# GSE_Controller_Schematic25_EasyEDA.net
KiCad netlist of a schematic drawn in EasyEDA
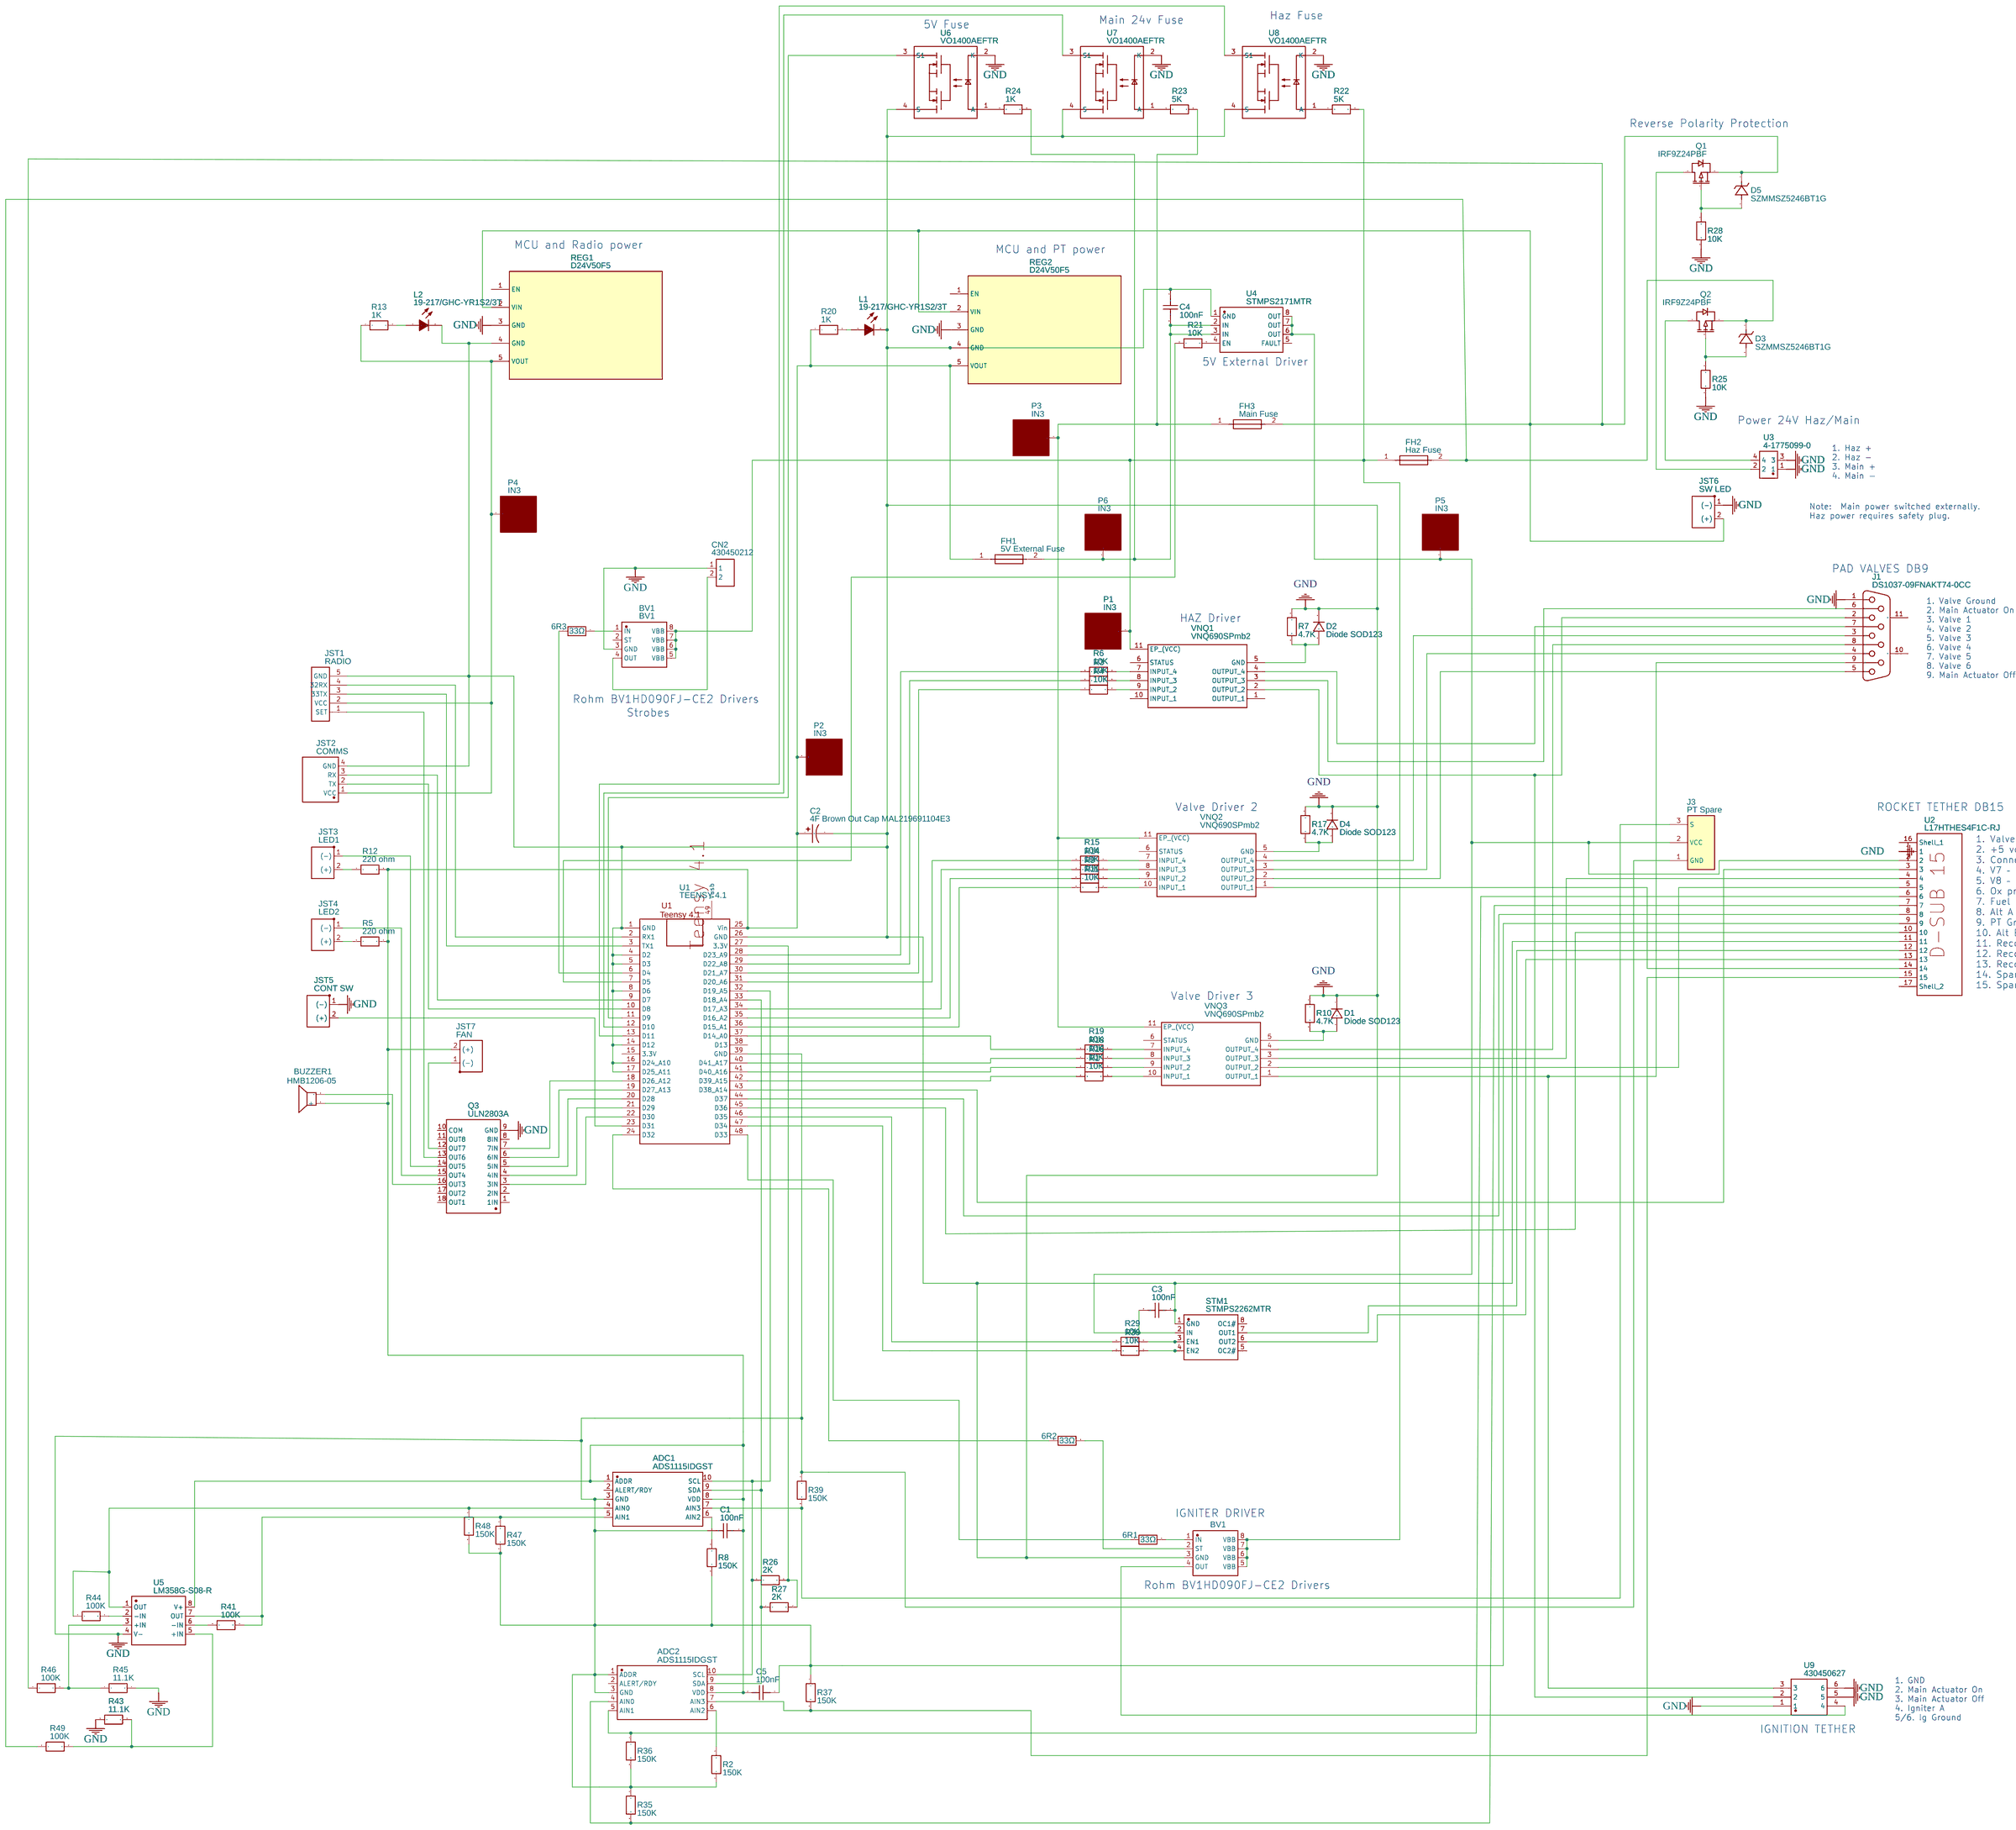
[diagram p0: schematic sheet]

(export (version "E")
  (design (tool "Eeschema 10.0.6"))
  (components
    (comp (ref "6R1")
      (value "33Ω")
      (fields (field (name "Manufacturer Part") "SFR03EZPF1001") (field (name "Manufacturer") "ROHM(罗姆)"))
      (libsource (lib "") (part "SFR03EZPF1001"))
    )
    (comp (ref "6R2")
      (value "33Ω")
      (fields (field (name "Manufacturer Part") "SFR03EZPF1001") (field (name "Manufacturer") "ROHM(罗姆)"))
      (libsource (lib "") (part "SFR03EZPF1001"))
    )
    (comp (ref "6R3")
      (value "33Ω")
      (fields (field (name "Manufacturer Part") "SFR03EZPF1001") (field (name "Manufacturer") "ROHM(罗姆)"))
      (libsource (lib "") (part "SFR03EZPF1001"))
    )
    (comp (ref "ADC1")
      (value "ADS1115IDGST")
      (fields (field (name "Manufacturer") "Texas Instruments"))
      (libsource (lib "") (part "ADS1115IDGST"))
    )
    (comp (ref "ADC2")
      (value "ADS1115IDGST")
      (fields (field (name "Manufacturer") "Texas Instruments"))
      (libsource (lib "") (part "ADS1115IDGST"))
    )
    (comp (ref "BUZZER1")
      (value "HMB1206-05")
      (fields (field (name "Manufacturer") "HNDZ"))
      (libsource (lib "") (part "HMB1206-05"))
    )
    (comp (ref "BV1")
      (value "BV1")
      (fields (field (name "Manufacturer Part") "BV1HD090FJ-CE2") (field (name "Manufacturer") "ROHM(罗姆)"))
      (libsource (lib "") (part "BV1HD090FJ-CE2"))
    )
    (comp (ref "BV2")
      (value "BV1")
      (fields (field (name "Manufacturer Part") "BV1HD090FJ-CE2") (field (name "Manufacturer") "ROHM(罗姆)"))
      (libsource (lib "") (part "BV1HD090FJ-CE2"))
    )
    (comp (ref "C1")
      (value "100nF")
      (fields (field (name "Manufacturer Part") "CC0402KRX7R6BB104") (field (name "Manufacturer") "YAGEO"))
      (libsource (lib "") (part "CC0402KRX7R6BB104"))
    )
    (comp (ref "C2") (value "4F Brown Out Cap MAL219691104E3") (libsource (lib "") (part "C_Tan_SMD_A_US")))
    (comp (ref "C3")
      (value "100nF")
      (fields (field (name "Manufacturer Part") "CC0402KRX7R6BB104") (field (name "Manufacturer") "YAGEO"))
      (libsource (lib "") (part "CC0402KRX7R6BB104"))
    )
    (comp (ref "C4")
      (value "100nF")
      (fields (field (name "Manufacturer Part") "CC0402KRX7R6BB104") (field (name "Manufacturer") "YAGEO"))
      (libsource (lib "") (part "CC0402KRX7R6BB104_1"))
    )
    (comp (ref "C5")
      (value "100nF")
      (fields (field (name "Manufacturer Part") "CC0402KRX7R6BB104") (field (name "Manufacturer") "YAGEO"))
      (libsource (lib "") (part "CC0402KRX7R6BB104"))
    )
    (comp (ref "CN2")
      (value "430450212")
      (fields (field (name "Manufacturer") "MOLEX"))
      (libsource (lib "") (part "430450212"))
    )
    (comp (ref "D1")
      (value "Diode SOD123")
      (fields
        (field (name "Manufacturer Part") "S15MLW RVG")
        (field (name "Manufacturer") "Taiwan Semiconductor(Taiwan Semicon)")
      )
      (libsource (lib "") (part "S15MLW RVG"))
    )
    (comp (ref "D2")
      (value "Diode SOD123")
      (fields
        (field (name "Manufacturer Part") "S15MLW RVG")
        (field (name "Manufacturer") "Taiwan Semiconductor(Taiwan Semicon)")
      )
      (libsource (lib "") (part "S15MLW RVG"))
    )
    (comp (ref "D3")
      (value "SZMMSZ5246BT1G")
      (fields (field (name "Manufacturer") "onsemi(安森美)"))
      (libsource (lib "") (part "SZMMSZ5246BT1G"))
    )
    (comp (ref "D4")
      (value "Diode SOD123")
      (fields
        (field (name "Manufacturer Part") "S15MLW RVG")
        (field (name "Manufacturer") "Taiwan Semiconductor(Taiwan Semicon)")
      )
      (libsource (lib "") (part "S15MLW RVG"))
    )
    (comp (ref "D5")
      (value "SZMMSZ5246BT1G")
      (fields (field (name "Manufacturer") "onsemi(安森美)"))
      (libsource (lib "") (part "SZMMSZ5246BT1G"))
    )
    (comp (ref "FH1")
      (value "5V External Fuse")
      (fields (field (name "Manufacturer Part") "01000063Z") (field (name "Manufacturer") "Littlefuse"))
      (libsource (lib "") (part "Mini Blade Fuse Holder"))
    )
    (comp (ref "FH2")
      (value "Haz Fuse")
      (fields (field (name "Manufacturer Part") "01000063Z") (field (name "Manufacturer") "Littlefuse"))
      (libsource (lib "") (part "Mini Blade Fuse Holder"))
    )
    (comp (ref "FH3")
      (value "Main Fuse")
      (fields (field (name "Manufacturer Part") "01000063Z") (field (name "Manufacturer") "Littlefuse"))
      (libsource (lib "") (part "Mini Blade Fuse Holder"))
    )
    (comp (ref "J1")
      (value "DS1037-09FNAKT74-0CC")
      (fields (field (name "Manufacturer") "CONNFLY"))
      (libsource (lib "") (part "DS1037-09FNAKT74-0CC"))
    )
    (comp (ref "J3")
      (value "PT Spare")
      (fields (field (name "Manufacturer Part") "B3B-PH-K-S(LF)(SN)") (field (name "Manufacturer") "JST"))
      (libsource (lib "") (part "Unknown_1000_-465"))
    )
    (comp (ref "JST1") (value "RADIO") (libsource (lib "") (part "JST-PH2.0-5PINS")))
    (comp (ref "JST2")
      (value "COMMS")
      (fields
        (field (name "Manufacturer Part") "B4B-PH-K(LF)(SN)")
        (field (name "Manufacturer") "JST Sales America")
      )
      (libsource (lib "") (part "Unknown_-515_-530"))
    )
    (comp (ref "JST3") (value "LED1") (libsource (lib "") (part "JST2X")))
    (comp (ref "JST4") (value "LED2") (libsource (lib "") (part "JST2X")))
    (comp (ref "JST5") (value "CONT SW") (libsource (lib "") (part "JST2X")))
    (comp (ref "JST6") (value "SW LED") (libsource (lib "") (part "JST2X")))
    (comp (ref "JST7") (value "FAN") (libsource (lib "") (part "JST2X_1")))
    (comp (ref "L1")
      (value "19-217/GHC-YR1S2/3T")
      (fields (field (name "Manufacturer") "EVERLIGHT"))
      (libsource (lib "") (part "19-217/GHC-YR1S2/3T"))
    )
    (comp (ref "L2")
      (value "19-217/GHC-YR1S2/3T")
      (fields (field (name "Manufacturer") "EVERLIGHT"))
      (libsource (lib "") (part "19-217/GHC-YR1S2/3T"))
    )
    (comp (ref "P1")
      (value "IN3")
      (fields (field (name "Manufacturer Part") "Soldering pad"))
      (libsource (lib "") (part "Solder Pad_1"))
    )
    (comp (ref "P2")
      (value "IN3")
      (fields (field (name "Manufacturer Part") "Soldering pad"))
      (libsource (lib "") (part "Solder Pad"))
    )
    (comp (ref "P3")
      (value "IN3")
      (fields (field (name "Manufacturer Part") "Soldering pad"))
      (libsource (lib "") (part "Solder Pad_1"))
    )
    (comp (ref "P4")
      (value "IN3")
      (fields (field (name "Manufacturer Part") "Soldering pad"))
      (libsource (lib "") (part "Solder Pad"))
    )
    (comp (ref "P5")
      (value "IN3")
      (fields (field (name "Manufacturer Part") "Soldering pad"))
      (libsource (lib "") (part "Solder Pad_2"))
    )
    (comp (ref "P6")
      (value "IN3")
      (fields (field (name "Manufacturer Part") "Soldering pad"))
      (libsource (lib "") (part "Solder Pad_2"))
    )
    (comp (ref "Q1")
      (value "IRF9Z24PBF")
      (fields (field (name "Manufacturer") "VISHAY(威世)"))
      (libsource (lib "") (part "IRF9Z24PBF"))
    )
    (comp (ref "Q2")
      (value "IRF9Z24PBF")
      (fields (field (name "Manufacturer") "VISHAY(威世)"))
      (libsource (lib "") (part "IRF9Z24PBF"))
    )
    (comp (ref "Q3")
      (value "ULN2803A")
      (fields (field (name "Manufacturer") "STMicroelectronics"))
      (libsource (lib "") (part "ULN2803A"))
    )
    (comp (ref "R1")
      (value "10K")
      (fields (field (name "Manufacturer Part") "ERJP06J221V") (field (name "Manufacturer") "PANASONIC"))
      (libsource (lib "") (part "ERJP06J221V"))
    )
    (comp (ref "R2")
      (value "150K")
      (fields (field (name "Manufacturer Part") "ERJP06J221V") (field (name "Manufacturer") "PANASONIC"))
      (libsource (lib "") (part "ERJP06J221V_1"))
    )
    (comp (ref "R3")
      (value "10K")
      (fields (field (name "Manufacturer Part") "ERJP06J221V") (field (name "Manufacturer") "PANASONIC"))
      (libsource (lib "") (part "ERJP06J221V"))
    )
    (comp (ref "R4")
      (value "10K")
      (fields (field (name "Manufacturer Part") "ERJP06J221V") (field (name "Manufacturer") "PANASONIC"))
      (libsource (lib "") (part "ERJP06J221V"))
    )
    (comp (ref "R5")
      (value "220 ohm")
      (fields (field (name "Manufacturer Part") "ERJP06J221V") (field (name "Manufacturer") "PANASONIC"))
      (libsource (lib "") (part "ERJP06J221V"))
    )
    (comp (ref "R6")
      (value "10K")
      (fields (field (name "Manufacturer Part") "ERJP06J221V") (field (name "Manufacturer") "PANASONIC"))
      (libsource (lib "") (part "ERJP06J221V"))
    )
    (comp (ref "R7")
      (value "4.7K")
      (fields (field (name "Manufacturer Part") "ERJP06J221V") (field (name "Manufacturer") "PANASONIC"))
      (libsource (lib "") (part "ERJP06J221V_1"))
    )
    (comp (ref "R8")
      (value "150K")
      (fields (field (name "Manufacturer Part") "ERJP06J221V") (field (name "Manufacturer") "PANASONIC"))
      (libsource (lib "") (part "ERJP06J221V_1"))
    )
    (comp (ref "R9")
      (value "10K")
      (fields (field (name "Manufacturer Part") "ERJP06J221V") (field (name "Manufacturer") "PANASONIC"))
      (libsource (lib "") (part "ERJP06J221V"))
    )
    (comp (ref "R10")
      (value "4.7K")
      (fields (field (name "Manufacturer Part") "ERJP06J221V") (field (name "Manufacturer") "PANASONIC"))
      (libsource (lib "") (part "ERJP06J221V_1"))
    )
    (comp (ref "R11")
      (value "10K")
      (fields (field (name "Manufacturer Part") "ERJP06J221V") (field (name "Manufacturer") "PANASONIC"))
      (libsource (lib "") (part "ERJP06J221V"))
    )
    (comp (ref "R12")
      (value "220 ohm")
      (fields (field (name "Manufacturer Part") "ERJP06J221V") (field (name "Manufacturer") "PANASONIC"))
      (libsource (lib "") (part "ERJP06J221V"))
    )
    (comp (ref "R13")
      (value "1K")
      (fields (field (name "Manufacturer Part") "ERJP06J221V") (field (name "Manufacturer") "PANASONIC"))
      (libsource (lib "") (part "ERJP06J221V"))
    )
    (comp (ref "R14")
      (value "10K")
      (fields (field (name "Manufacturer Part") "ERJP06J221V") (field (name "Manufacturer") "PANASONIC"))
      (libsource (lib "") (part "ERJP06J221V"))
    )
    (comp (ref "R15")
      (value "10K")
      (fields (field (name "Manufacturer Part") "ERJP06J221V") (field (name "Manufacturer") "PANASONIC"))
      (libsource (lib "") (part "ERJP06J221V"))
    )
    (comp (ref "R16")
      (value "10K")
      (fields (field (name "Manufacturer Part") "ERJP06J221V") (field (name "Manufacturer") "PANASONIC"))
      (libsource (lib "") (part "ERJP06J221V"))
    )
    (comp (ref "R17")
      (value "4.7K")
      (fields (field (name "Manufacturer Part") "ERJP06J221V") (field (name "Manufacturer") "PANASONIC"))
      (libsource (lib "") (part "ERJP06J221V_1"))
    )
    (comp (ref "R18")
      (value "10K")
      (fields (field (name "Manufacturer Part") "ERJP06J221V") (field (name "Manufacturer") "PANASONIC"))
      (libsource (lib "") (part "ERJP06J221V"))
    )
    (comp (ref "R19")
      (value "10K")
      (fields (field (name "Manufacturer Part") "ERJP06J221V") (field (name "Manufacturer") "PANASONIC"))
      (libsource (lib "") (part "ERJP06J221V"))
    )
    (comp (ref "R20")
      (value "1K")
      (fields (field (name "Manufacturer Part") "ERJP06J221V") (field (name "Manufacturer") "PANASONIC"))
      (libsource (lib "") (part "ERJP06J221V"))
    )
    (comp (ref "R21")
      (value "10K")
      (fields (field (name "Manufacturer Part") "ERJP06J221V") (field (name "Manufacturer") "PANASONIC"))
      (libsource (lib "") (part "ERJP06J221V"))
    )
    (comp (ref "R22")
      (value "5K")
      (fields (field (name "Manufacturer Part") "ERJP06J221V") (field (name "Manufacturer") "PANASONIC"))
      (libsource (lib "") (part "ERJP06J221V"))
    )
    (comp (ref "R23")
      (value "5K")
      (fields (field (name "Manufacturer Part") "ERJP06J221V") (field (name "Manufacturer") "PANASONIC"))
      (libsource (lib "") (part "ERJP06J221V"))
    )
    (comp (ref "R24")
      (value "1K")
      (fields (field (name "Manufacturer Part") "ERJP06J221V") (field (name "Manufacturer") "PANASONIC"))
      (libsource (lib "") (part "ERJP06J221V"))
    )
    (comp (ref "R25")
      (value "10K")
      (fields (field (name "Manufacturer Part") "ERJP06J221V") (field (name "Manufacturer") "PANASONIC"))
      (libsource (lib "") (part "ERJP06J221V_1"))
    )
    (comp (ref "R26")
      (value "2K")
      (fields (field (name "Manufacturer Part") "ERJP06J221V") (field (name "Manufacturer") "PANASONIC"))
      (libsource (lib "") (part "ERJP06J221V"))
    )
    (comp (ref "R27")
      (value "2K")
      (fields (field (name "Manufacturer Part") "ERJP06J221V") (field (name "Manufacturer") "PANASONIC"))
      (libsource (lib "") (part "ERJP06J221V"))
    )
    (comp (ref "R28")
      (value "10K")
      (fields (field (name "Manufacturer Part") "ERJP06J221V") (field (name "Manufacturer") "PANASONIC"))
      (libsource (lib "") (part "ERJP06J221V_1"))
    )
    (comp (ref "R29")
      (value "10K")
      (fields (field (name "Manufacturer Part") "ERJP06J221V") (field (name "Manufacturer") "PANASONIC"))
      (libsource (lib "") (part "ERJP06J221V"))
    )
    (comp (ref "R30")
      (value "10K")
      (fields (field (name "Manufacturer Part") "ERJP06J221V") (field (name "Manufacturer") "PANASONIC"))
      (libsource (lib "") (part "ERJP06J221V"))
    )
    (comp (ref "R35")
      (value "150K")
      (fields (field (name "Manufacturer Part") "ERJP06J221V") (field (name "Manufacturer") "PANASONIC"))
      (libsource (lib "") (part "ERJP06J221V_1"))
    )
    (comp (ref "R36")
      (value "150K")
      (fields (field (name "Manufacturer Part") "ERJP06J221V") (field (name "Manufacturer") "PANASONIC"))
      (libsource (lib "") (part "ERJP06J221V_1"))
    )
    (comp (ref "R37")
      (value "150K")
      (fields (field (name "Manufacturer Part") "ERJP06J221V") (field (name "Manufacturer") "PANASONIC"))
      (libsource (lib "") (part "ERJP06J221V_1"))
    )
    (comp (ref "R39")
      (value "150K")
      (fields (field (name "Manufacturer Part") "ERJP06J221V") (field (name "Manufacturer") "PANASONIC"))
      (libsource (lib "") (part "ERJP06J221V_1"))
    )
    (comp (ref "R41")
      (value "100K")
      (fields (field (name "Manufacturer Part") "ERJP06J221V") (field (name "Manufacturer") "PANASONIC"))
      (libsource (lib "") (part "ERJP06J221V"))
    )
    (comp (ref "R43")
      (value "11.1K")
      (fields (field (name "Manufacturer Part") "ERJP06J221V") (field (name "Manufacturer") "PANASONIC"))
      (libsource (lib "") (part "ERJP06J221V"))
    )
    (comp (ref "R44")
      (value "100K")
      (fields (field (name "Manufacturer Part") "ERJP06J221V") (field (name "Manufacturer") "PANASONIC"))
      (libsource (lib "") (part "ERJP06J221V"))
    )
    (comp (ref "R45")
      (value "11.1K")
      (fields (field (name "Manufacturer Part") "ERJP06J221V") (field (name "Manufacturer") "PANASONIC"))
      (libsource (lib "") (part "ERJP06J221V"))
    )
    (comp (ref "R46")
      (value "100K")
      (fields (field (name "Manufacturer Part") "ERJP06J221V") (field (name "Manufacturer") "PANASONIC"))
      (libsource (lib "") (part "ERJP06J221V"))
    )
    (comp (ref "R47")
      (value "150K")
      (fields (field (name "Manufacturer Part") "ERJP06J221V") (field (name "Manufacturer") "PANASONIC"))
      (libsource (lib "") (part "ERJP06J221V_1"))
    )
    (comp (ref "R48")
      (value "150K")
      (fields (field (name "Manufacturer Part") "ERJP06J221V") (field (name "Manufacturer") "PANASONIC"))
      (libsource (lib "") (part "ERJP06J221V_1"))
    )
    (comp (ref "R49")
      (value "100K")
      (fields (field (name "Manufacturer Part") "ERJP06J221V") (field (name "Manufacturer") "PANASONIC"))
      (libsource (lib "") (part "ERJP06J221V"))
    )
    (comp (ref "REG1") (value "D24V50F5") (libsource (lib "") (part "D24V50F5")))
    (comp (ref "REG2") (value "D24V50F5") (libsource (lib "") (part "D24V50F5")))
    (comp (ref "STM1")
      (value "STMPS2262MTR")
      (fields (field (name "Manufacturer") "ST(意法半导体)"))
      (libsource (lib "") (part "STMPS2262MTR"))
    )
    (comp (ref "U1") (value "TEENSY 4.1") (libsource (lib "") (part "TEENSY 4.1")))
    (comp (ref "U2") (value "L17HTHES4F1C-RJ") (libsource (lib "") (part "L17HTHES4F1C-RJ")))
    (comp (ref "U3")
      (value "4-1775099-0")
      (fields (field (name "Manufacturer") "TE Connectivity(美国泰科)"))
      (libsource (lib "") (part "4-1775099-0"))
    )
    (comp (ref "U4")
      (value "STMPS2171MTR")
      (fields (field (name "Manufacturer") "ST(意法半导体)"))
      (libsource (lib "") (part "STMPS2171MTR"))
    )
    (comp (ref "U5")
      (value "LM358G-S08-R")
      (fields (field (name "Manufacturer") "UTC"))
      (libsource (lib "") (part "LM358G-S08-R"))
    )
    (comp (ref "U6")
      (value "VO1400AEFTR")
      (fields (field (name "Manufacturer") "VISHAY(威世)"))
      (libsource (lib "") (part "VO1400AEFTR"))
    )
    (comp (ref "U7")
      (value "VO1400AEFTR")
      (fields (field (name "Manufacturer") "VISHAY(威世)"))
      (libsource (lib "") (part "VO1400AEFTR"))
    )
    (comp (ref "U8")
      (value "VO1400AEFTR")
      (fields (field (name "Manufacturer") "VISHAY(威世)"))
      (libsource (lib "") (part "VO1400AEFTR"))
    )
    (comp (ref "U9")
      (value "430450627")
      (fields (field (name "Manufacturer") "MOLEX"))
      (libsource (lib "") (part "430450627"))
    )
    (comp (ref "VNQ1") (value "VNQ690SPmb2") (libsource (lib "") (part "VNQ690SPmb2")))
    (comp (ref "VNQ2") (value "VNQ690SPmb2") (libsource (lib "") (part "VNQ690SPmb2")))
    (comp (ref "VNQ3") (value "VNQ690SPmb2") (libsource (lib "") (part "VNQ690SPmb2")))
  )
  (nets
    (net (code "1") (name "GND") (class "Default")
      (node (ref "ADC1") (pin "3") (pinfunction "GND_3") (pintype "unspecified"))
      (node (ref "ADC2") (pin "1") (pinfunction "ADDR_1") (pintype "unspecified"))
      (node (ref "ADC2") (pin "3") (pinfunction "GND_3") (pintype "unspecified"))
      (node (ref "BV1") (pin "3") (pinfunction "GND_3") (pintype "unspecified"))
      (node (ref "BV2") (pin "3") (pinfunction "GND_3") (pintype "unspecified"))
      (node (ref "C1") (pin "2") (pinfunction "2_2") (pintype "unspecified"))
      (node (ref "C2") (pin "2") (pinfunction "2_2") (pintype "unspecified"))
      (node (ref "C3") (pin "1") (pinfunction "1_1") (pintype "unspecified"))
      (node (ref "C4") (pin "1") (pinfunction "1_1") (pintype "unspecified"))
      (node (ref "C5") (pin "1") (pinfunction "1_1") (pintype "unspecified"))
      (node (ref "CN2") (pin "1") (pinfunction "1_1") (pintype "unspecified"))
      (node (ref "D1") (pin "1") (pinfunction "1_1") (pintype "unspecified"))
      (node (ref "D2") (pin "1") (pinfunction "1_1") (pintype "unspecified"))
      (node (ref "D4") (pin "1") (pinfunction "1_1") (pintype "unspecified"))
      (node (ref "J1") (pin "1") (pinfunction "1_1") (pintype "input"))
      (node (ref "J3") (pin "1") (pinfunction "GND_1") (pintype "input"))
      (node (ref "JST1") (pin "5") (pinfunction "GND_5") (pintype "unspecified"))
      (node (ref "JST2") (pin "4") (pinfunction "GND_4") (pintype "unspecified"))
      (node (ref "JST5") (pin "1") (pinfunction "(-)_1") (pintype "unspecified"))
      (node (ref "JST6") (pin "1") (pinfunction "(-)_1") (pintype "unspecified"))
      (node (ref "L1") (pin "2") (pinfunction "C_2") (pintype "input"))
      (node (ref "L2") (pin "2") (pinfunction "C_2") (pintype "input"))
      (node (ref "Q3") (pin "9") (pinfunction "GND_9") (pintype "unspecified"))
      (node (ref "R10") (pin "1") (pinfunction "1_1") (pintype "unspecified"))
      (node (ref "R17") (pin "1") (pinfunction "1_1") (pintype "unspecified"))
      (node (ref "R2") (pin "2") (pinfunction "2_2") (pintype "unspecified"))
      (node (ref "R25") (pin "2") (pinfunction "2_2") (pintype "unspecified"))
      (node (ref "R28") (pin "2") (pinfunction "2_2") (pintype "unspecified"))
      (node (ref "R35") (pin "1") (pinfunction "1_1") (pintype "unspecified"))
      (node (ref "R36") (pin "2") (pinfunction "2_2") (pintype "unspecified"))
      (node (ref "R37") (pin "1") (pinfunction "1_1") (pintype "unspecified"))
      (node (ref "R39") (pin "1") (pinfunction "1_1") (pintype "unspecified"))
      (node (ref "R43") (pin "1") (pinfunction "1_1") (pintype "unspecified"))
      (node (ref "R45") (pin "2") (pinfunction "2_2") (pintype "unspecified"))
      (node (ref "R47") (pin "2") (pinfunction "2_2") (pintype "unspecified"))
      (node (ref "R48") (pin "2") (pinfunction "2_2") (pintype "unspecified"))
      (node (ref "R7") (pin "1") (pinfunction "1_1") (pintype "unspecified"))
      (node (ref "R8") (pin "2") (pinfunction "2_2") (pintype "unspecified"))
      (node (ref "REG1") (pin "3") (pinfunction "GND_3") (pintype "unspecified"))
      (node (ref "REG1") (pin "4") (pinfunction "GND_4") (pintype "unspecified"))
      (node (ref "REG2") (pin "3") (pinfunction "GND_3") (pintype "unspecified"))
      (node (ref "REG2") (pin "4") (pinfunction "GND_4") (pintype "unspecified"))
      (node (ref "STM1") (pin "1") (pinfunction "GND_1") (pintype "unspecified"))
      (node (ref "U1") (pin "1") (pinfunction "GND_1") (pintype "unspecified"))
      (node (ref "U1") (pin "14") (pinfunction "D12_14") (pintype "unspecified"))
      (node (ref "U1") (pin "16") (pinfunction "D24_A10_16") (pintype "unspecified"))
      (node (ref "U1") (pin "17") (pinfunction "D25_A11_17") (pintype "unspecified"))
      (node (ref "U1") (pin "26") (pinfunction "GND_26") (pintype "unspecified"))
      (node (ref "U1") (pin "39") (pinfunction "GND_39") (pintype "unspecified"))
      (node (ref "U1") (pin "4") (pinfunction "D2_4") (pintype "unspecified"))
      (node (ref "U1") (pin "5") (pinfunction "D3_5") (pintype "unspecified"))
      (node (ref "U1") (pin "8") (pinfunction "D6_8") (pintype "unspecified"))
      (node (ref "U2") (pin "1") (pinfunction "1_1") (pintype "unspecified"))
      (node (ref "U2") (pin "11") (pinfunction "11_11") (pintype "unspecified"))
      (node (ref "U2") (pin "9") (pinfunction "9_9") (pintype "unspecified"))
      (node (ref "U3") (pin "1") (pinfunction "1_1") (pintype "unspecified"))
      (node (ref "U3") (pin "3") (pinfunction "3_3") (pintype "unspecified"))
      (node (ref "U4") (pin "1") (pinfunction "GND_1") (pintype "unspecified"))
      (node (ref "U5") (pin "4") (pinfunction "V-_4") (pintype "unspecified"))
      (node (ref "U6") (pin "2") (pinfunction "K_2") (pintype "unspecified"))
      (node (ref "U6") (pin "4") (pinfunction "S_4") (pintype "unspecified"))
      (node (ref "U7") (pin "2") (pinfunction "K_2") (pintype "unspecified"))
      (node (ref "U7") (pin "4") (pinfunction "S_4") (pintype "unspecified"))
      (node (ref "U8") (pin "2") (pinfunction "K_2") (pintype "unspecified"))
      (node (ref "U8") (pin "4") (pinfunction "S_4") (pintype "unspecified"))
      (node (ref "U9") (pin "1") (pinfunction "1_1") (pintype "unspecified"))
      (node (ref "U9") (pin "5") (pinfunction "5_5") (pintype "unspecified"))
      (node (ref "U9") (pin "6") (pinfunction "6_6") (pintype "unspecified"))
    )
    (net (code "2") (name "Net-(ADC1-ADDR)") (class "Default")
      (node (ref "ADC1") (pin "1") (pinfunction "ADDR_1") (pintype "unspecified"))
      (node (ref "ADC1") (pin "8") (pinfunction "VDD_8") (pintype "unspecified"))
      (node (ref "ADC2") (pin "8") (pinfunction "VDD_8") (pintype "unspecified"))
      (node (ref "BUZZER1") (pin "1") (pinfunction "+_1") (pintype "unspecified"))
      (node (ref "C1") (pin "1") (pinfunction "1_1") (pintype "unspecified"))
      (node (ref "C2") (pin "1") (pinfunction "1_1") (pintype "unspecified"))
      (node (ref "C5") (pin "2") (pinfunction "2_2") (pintype "unspecified"))
      (node (ref "FH1") (pin "1") (pinfunction "1_1") (pintype "unspecified"))
      (node (ref "JST7") (pin "2") (pinfunction "(+)_2") (pintype "unspecified"))
      (node (ref "P2") (pin "1") (pinfunction "1_1") (pintype "unspecified"))
      (node (ref "R12") (pin "2") (pinfunction "2_2") (pintype "unspecified"))
      (node (ref "R20") (pin "1") (pinfunction "1_1") (pintype "unspecified"))
      (node (ref "R5") (pin "2") (pinfunction "2_2") (pintype "unspecified"))
      (node (ref "REG2") (pin "5") (pinfunction "VOUT_5") (pintype "unspecified"))
      (node (ref "U1") (pin "25") (pinfunction "Vin_25") (pintype "unspecified"))
      (node (ref "U5") (pin "8") (pinfunction "V+_8") (pintype "unspecified"))
    )
    (net (code "3") (name "Net-(ADC1-AIN0)") (class "Default")
      (node (ref "ADC1") (pin "4") (pinfunction "AIN0_4") (pintype "unspecified"))
      (node (ref "R44") (pin "1") (pinfunction "1_1") (pintype "unspecified"))
      (node (ref "R48") (pin "1") (pinfunction "1_1") (pintype "unspecified"))
      (node (ref "U5") (pin "1") (pinfunction "OUT_1") (pintype "unspecified"))
    )
    (net (code "4") (name "Net-(ADC1-AIN1)") (class "Default")
      (node (ref "ADC1") (pin "5") (pinfunction "AIN1_5") (pintype "unspecified"))
      (node (ref "R41") (pin "2") (pinfunction "2_2") (pintype "unspecified"))
      (node (ref "R47") (pin "1") (pinfunction "1_1") (pintype "unspecified"))
      (node (ref "U5") (pin "7") (pinfunction "OUT_7") (pintype "unspecified"))
    )
    (net (code "5") (name "Net-(ADC1-AIN2)") (class "Default")
      (node (ref "ADC1") (pin "6") (pinfunction "AIN2_6") (pintype "unspecified"))
      (node (ref "R8") (pin "1") (pinfunction "1_1") (pintype "unspecified"))
    )
    (net (code "6") (name "Net-(ADC1-AIN3)") (class "Default")
      (node (ref "ADC1") (pin "7") (pinfunction "AIN3_7") (pintype "unspecified"))
      (node (ref "J3") (pin "3") (pinfunction "S_3") (pintype "input"))
      (node (ref "R39") (pin "2") (pinfunction "2_2") (pintype "unspecified"))
    )
    (net (code "7") (name "Net-(ADC1-SCL)") (class "Default")
      (node (ref "ADC1") (pin "10") (pinfunction "SCL_10") (pintype "unspecified"))
      (node (ref "ADC2") (pin "10") (pinfunction "SCL_10") (pintype "unspecified"))
      (node (ref "R26") (pin "1") (pinfunction "1_1") (pintype "unspecified"))
      (node (ref "U1") (pin "32") (pinfunction "D19_A5_32") (pintype "unspecified"))
    )
    (net (code "8") (name "Net-(ADC1-SDA)") (class "Default")
      (node (ref "ADC1") (pin "9") (pinfunction "SDA_9") (pintype "unspecified"))
      (node (ref "ADC2") (pin "9") (pinfunction "SDA_9") (pintype "unspecified"))
      (node (ref "R27") (pin "1") (pinfunction "1_1") (pintype "unspecified"))
      (node (ref "U1") (pin "33") (pinfunction "D18_A4_33") (pintype "unspecified"))
    )
    (net (code "9") (name "Net-(ADC2-AIN0)") (class "Default")
      (node (ref "ADC2") (pin "4") (pinfunction "AIN0_4") (pintype "unspecified"))
      (node (ref "R35") (pin "2") (pinfunction "2_2") (pintype "unspecified"))
      (node (ref "U2") (pin "7") (pinfunction "7_7") (pintype "unspecified"))
    )
    (net (code "10") (name "Net-(ADC2-AIN1)") (class "Default")
      (node (ref "ADC2") (pin "5") (pinfunction "AIN1_5") (pintype "unspecified"))
      (node (ref "R36") (pin "1") (pinfunction "1_1") (pintype "unspecified"))
      (node (ref "U2") (pin "6") (pinfunction "6_6") (pintype "unspecified"))
    )
    (net (code "11") (name "Net-(ADC2-AIN2)") (class "Default")
      (node (ref "ADC2") (pin "6") (pinfunction "AIN2_6") (pintype "unspecified"))
      (node (ref "R2") (pin "1") (pinfunction "1_1") (pintype "unspecified"))
    )
    (net (code "12") (name "Net-(ADC2-AIN3)") (class "Default")
      (node (ref "ADC2") (pin "7") (pinfunction "AIN3_7") (pintype "unspecified"))
      (node (ref "R37") (pin "2") (pinfunction "2_2") (pintype "unspecified"))
      (node (ref "U2") (pin "15") (pinfunction "15_15") (pintype "unspecified"))
    )
    (net (code "13") (name "Net-(BV1-IN)") (class "Default")
      (node (ref "6R3") (pin "2") (pinfunction "2_2") (pintype "unspecified"))
      (node (ref "BV1") (pin "1") (pinfunction "IN_1") (pintype "unspecified"))
    )
    (net (code "14") (name "Net-(BV1-OUT)") (class "Default")
      (node (ref "BV1") (pin "4") (pinfunction "OUT_4") (pintype "unspecified"))
      (node (ref "CN2") (pin "2") (pinfunction "2_2") (pintype "unspecified"))
    )
    (net (code "15") (name "Net-(BV2-IN)") (class "Default")
      (node (ref "6R1") (pin "2") (pinfunction "2_2") (pintype "unspecified"))
      (node (ref "BV2") (pin "1") (pinfunction "IN_1") (pintype "unspecified"))
    )
    (net (code "16") (name "Net-(BV2-OUT)") (class "Default")
      (node (ref "BV2") (pin "4") (pinfunction "OUT_4") (pintype "unspecified"))
      (node (ref "U9") (pin "4") (pinfunction "4_4") (pintype "unspecified"))
    )
    (net (code "17") (name "Net-(BV2-ST)") (class "Default")
      (node (ref "6R2") (pin "2") (pinfunction "2_2") (pintype "unspecified"))
      (node (ref "BV2") (pin "2") (pinfunction "ST_2") (pintype "unspecified"))
    )
    (net (code "18") (name "Net-(C4-Pad2)") (class "Default")
      (node (ref "C4") (pin "2") (pinfunction "2_2") (pintype "unspecified"))
      (node (ref "FH1") (pin "2") (pinfunction "2_2") (pintype "unspecified"))
      (node (ref "P6") (pin "1") (pinfunction "1_1") (pintype "unspecified"))
      (node (ref "R24") (pin "2") (pinfunction "2_2") (pintype "unspecified"))
      (node (ref "U4") (pin "2") (pinfunction "IN_2") (pintype "unspecified"))
      (node (ref "U4") (pin "3") (pinfunction "IN_3") (pintype "unspecified"))
    )
    (net (code "19") (name "Net-(D3-A)") (class "Default")
      (node (ref "D3") (pin "2") (pinfunction "A_2") (pintype "unspecified"))
      (node (ref "Q2") (pin "1") (pinfunction "G_1") (pintype "unspecified"))
      (node (ref "R25") (pin "1") (pinfunction "1_1") (pintype "unspecified"))
    )
    (net (code "20") (name "Net-(D3-C)") (class "Default")
      (node (ref "D3") (pin "1") (pinfunction "C_1") (pintype "unspecified"))
      (node (ref "FH2") (pin "2") (pinfunction "2_2") (pintype "unspecified"))
      (node (ref "Q2") (pin "3") (pinfunction "S_3") (pintype "unspecified"))
      (node (ref "R49") (pin "1") (pinfunction "1_1") (pintype "unspecified"))
    )
    (net (code "21") (name "Net-(D5-A)") (class "Default")
      (node (ref "D5") (pin "2") (pinfunction "A_2") (pintype "unspecified"))
      (node (ref "Q1") (pin "1") (pinfunction "G_1") (pintype "unspecified"))
      (node (ref "R28") (pin "1") (pinfunction "1_1") (pintype "unspecified"))
    )
    (net (code "22") (name "Net-(D5-C)") (class "Default")
      (node (ref "D5") (pin "1") (pinfunction "C_1") (pintype "unspecified"))
      (node (ref "FH3") (pin "2") (pinfunction "2_2") (pintype "unspecified"))
      (node (ref "JST6") (pin "2") (pinfunction "(+)_2") (pintype "unspecified"))
      (node (ref "Q1") (pin "3") (pinfunction "S_3") (pintype "unspecified"))
      (node (ref "R46") (pin "1") (pinfunction "1_1") (pintype "unspecified"))
      (node (ref "REG1") (pin "2") (pinfunction "VIN_2") (pintype "unspecified"))
      (node (ref "REG2") (pin "2") (pinfunction "VIN_2") (pintype "unspecified"))
    )
    (net (code "23") (name "Net-(J3-VCC)") (class "Default")
      (node (ref "C3") (pin "2") (pinfunction "2_2") (pintype "unspecified"))
      (node (ref "J3") (pin "2") (pinfunction "VCC_2") (pintype "input"))
      (node (ref "P5") (pin "1") (pinfunction "1_1") (pintype "unspecified"))
      (node (ref "STM1") (pin "2") (pinfunction "IN_2") (pintype "unspecified"))
      (node (ref "U2") (pin "2") (pinfunction "2_2") (pintype "unspecified"))
      (node (ref "U4") (pin "6") (pinfunction "OUT_6") (pintype "unspecified"))
      (node (ref "U4") (pin "7") (pinfunction "OUT_7") (pintype "unspecified"))
      (node (ref "U4") (pin "8") (pinfunction "OUT_8") (pintype "unspecified"))
    )
    (net (code "24") (name "Net-(JST1-32RX)") (class "Default")
      (node (ref "JST1") (pin "4") (pinfunction "32RX_4") (pintype "unspecified"))
      (node (ref "U1") (pin "2") (pinfunction "RX1_2") (pintype "unspecified"))
    )
    (net (code "25") (name "Net-(JST1-33TX)") (class "Default")
      (node (ref "JST1") (pin "3") (pinfunction "33TX_3") (pintype "unspecified"))
      (node (ref "U1") (pin "3") (pinfunction "TX1_3") (pintype "unspecified"))
    )
    (net (code "26") (name "Net-(JST1-SET)") (class "Default")
      (node (ref "JST1") (pin "1") (pinfunction "SET_1") (pintype "unspecified"))
      (node (ref "Q3") (pin "13") (pinfunction "OUT6_13") (pintype "unspecified"))
    )
    (net (code "27") (name "Net-(JST1-VCC)") (class "Default")
      (node (ref "JST1") (pin "2") (pinfunction "VCC_2") (pintype "unspecified"))
      (node (ref "JST2") (pin "1") (pinfunction "VCC_1") (pintype "unspecified"))
      (node (ref "P4") (pin "1") (pinfunction "1_1") (pintype "unspecified"))
      (node (ref "R13") (pin "1") (pinfunction "1_1") (pintype "unspecified"))
      (node (ref "REG1") (pin "5") (pinfunction "VOUT_5") (pintype "unspecified"))
    )
    (net (code "28") (name "Net-(JST2-RX)") (class "Default")
      (node (ref "JST2") (pin "3") (pinfunction "RX_3") (pintype "unspecified"))
      (node (ref "U1") (pin "9") (pinfunction "D7_9") (pintype "unspecified"))
    )
    (net (code "29") (name "Net-(JST2-TX)") (class "Default")
      (node (ref "JST2") (pin "2") (pinfunction "TX_2") (pintype "unspecified"))
      (node (ref "U1") (pin "10") (pinfunction "D8_10") (pintype "unspecified"))
    )
    (net (code "30") (name "Net-(JST3-(+))") (class "Default")
      (node (ref "JST3") (pin "2") (pinfunction "(+)_2") (pintype "unspecified"))
      (node (ref "R12") (pin "1") (pinfunction "1_1") (pintype "unspecified"))
    )
    (net (code "31") (name "Net-(JST3-(-))") (class "Default")
      (node (ref "JST3") (pin "1") (pinfunction "(-)_1") (pintype "unspecified"))
      (node (ref "Q3") (pin "14") (pinfunction "OUT5_14") (pintype "unspecified"))
    )
    (net (code "32") (name "Net-(JST4-(+))") (class "Default")
      (node (ref "JST4") (pin "2") (pinfunction "(+)_2") (pintype "unspecified"))
      (node (ref "R5") (pin "1") (pinfunction "1_1") (pintype "unspecified"))
    )
    (net (code "33") (name "Net-(JST4-(-))") (class "Default")
      (node (ref "JST4") (pin "1") (pinfunction "(-)_1") (pintype "unspecified"))
      (node (ref "Q3") (pin "15") (pinfunction "OUT4_15") (pintype "unspecified"))
    )
    (net (code "34") (name "Net-(JST5-(+))") (class "Default")
      (node (ref "JST5") (pin "2") (pinfunction "(+)_2") (pintype "unspecified"))
      (node (ref "U1") (pin "23") (pinfunction "D31_23") (pintype "unspecified"))
    )
    (net (code "35") (name "Net-(JST7-(-))") (class "Default")
      (node (ref "JST7") (pin "1") (pinfunction "(-)_1") (pintype "unspecified"))
      (node (ref "Q3") (pin "12") (pinfunction "OUT7_12") (pintype "unspecified"))
    )
    (net (code "36") (name "Net-(L1-A)") (class "Default")
      (node (ref "L1") (pin "1") (pinfunction "A_1") (pintype "input"))
      (node (ref "R20") (pin "2") (pinfunction "2_2") (pintype "unspecified"))
    )
    (net (code "37") (name "Net-(L2-A)") (class "Default")
      (node (ref "L2") (pin "1") (pinfunction "A_1") (pintype "input"))
      (node (ref "R13") (pin "2") (pinfunction "2_2") (pintype "unspecified"))
    )
    (net (code "38") (name "Net-(Q1-D)") (class "Default")
      (node (ref "Q1") (pin "2") (pinfunction "D_2") (pintype "unspecified"))
      (node (ref "U3") (pin "2") (pinfunction "2_2") (pintype "unspecified"))
    )
    (net (code "39") (name "Net-(Q2-D)") (class "Default")
      (node (ref "Q2") (pin "2") (pinfunction "D_2") (pintype "unspecified"))
      (node (ref "U3") (pin "4") (pinfunction "4_4") (pintype "unspecified"))
    )
    (net (code "40") (name "Net-(Q3-3IN)") (class "Default")
      (node (ref "Q3") (pin "3") (pinfunction "3IN_3") (pintype "unspecified"))
      (node (ref "U1") (pin "22") (pinfunction "D30_22") (pintype "unspecified"))
    )
    (net (code "41") (name "Net-(Q3-4IN)") (class "Default")
      (node (ref "Q3") (pin "4") (pinfunction "4IN_4") (pintype "unspecified"))
      (node (ref "U1") (pin "21") (pinfunction "D29_21") (pintype "unspecified"))
    )
    (net (code "42") (name "Net-(Q3-5IN)") (class "Default")
      (node (ref "Q3") (pin "5") (pinfunction "5IN_5") (pintype "unspecified"))
      (node (ref "U1") (pin "20") (pinfunction "D28_20") (pintype "unspecified"))
    )
    (net (code "43") (name "Net-(Q3-6IN)") (class "Default")
      (node (ref "Q3") (pin "6") (pinfunction "6IN_6") (pintype "unspecified"))
      (node (ref "U1") (pin "19") (pinfunction "D27_A13_19") (pintype "unspecified"))
    )
    (net (code "44") (name "Net-(Q3-7IN)") (class "Default")
      (node (ref "Q3") (pin "7") (pinfunction "7IN_7") (pintype "unspecified"))
      (node (ref "U1") (pin "18") (pinfunction "D26_A12_18") (pintype "unspecified"))
    )
    (net (code "45") (name "Net-(Q3-OUT3)") (class "Default")
      (node (ref "BUZZER1") (pin "2") (pinfunction "2_2") (pintype "unspecified"))
      (node (ref "Q3") (pin "16") (pinfunction "OUT3_16") (pintype "unspecified"))
    )
    (net (code "46") (name "Net-(R26-Pad2)") (class "Default")
      (node (ref "R26") (pin "2") (pinfunction "2_2") (pintype "unspecified"))
      (node (ref "R27") (pin "2") (pinfunction "2_2") (pintype "unspecified"))
      (node (ref "U1") (pin "27") (pinfunction "3.3V_27") (pintype "unspecified"))
    )
    (net (code "47") (name "Net-(R41-Pad1)") (class "Default")
      (node (ref "R41") (pin "1") (pinfunction "1_1") (pintype "unspecified"))
      (node (ref "U5") (pin "6") (pinfunction "-IN_6") (pintype "unspecified"))
    )
    (net (code "48") (name "Net-(R43-Pad2)") (class "Default")
      (node (ref "R43") (pin "2") (pinfunction "2_2") (pintype "unspecified"))
      (node (ref "R49") (pin "2") (pinfunction "2_2") (pintype "unspecified"))
      (node (ref "U5") (pin "5") (pinfunction "+IN_5") (pintype "unspecified"))
    )
    (net (code "49") (name "Net-(R44-Pad2)") (class "Default")
      (node (ref "R44") (pin "2") (pinfunction "2_2") (pintype "unspecified"))
      (node (ref "U5") (pin "2") (pinfunction "-IN_2") (pintype "unspecified"))
    )
    (net (code "50") (name "Net-(R45-Pad1)") (class "Default")
      (node (ref "R45") (pin "1") (pinfunction "1_1") (pintype "unspecified"))
      (node (ref "R46") (pin "2") (pinfunction "2_2") (pintype "unspecified"))
      (node (ref "U5") (pin "3") (pinfunction "+IN_3") (pintype "unspecified"))
    )
    (net (code "51") (name "Net-(STM1-EN1)") (class "Default")
      (node (ref "R29") (pin "2") (pinfunction "2_2") (pintype "unspecified"))
      (node (ref "STM1") (pin "3") (pinfunction "EN1_3") (pintype "unspecified"))
    )
    (net (code "52") (name "Net-(STM1-EN2)") (class "Default")
      (node (ref "R30") (pin "2") (pinfunction "2_2") (pintype "unspecified"))
      (node (ref "STM1") (pin "4") (pinfunction "EN2_4") (pintype "unspecified"))
    )
    (net (code "53") (name "Net-(STM1-OUT1)") (class "Default")
      (node (ref "STM1") (pin "7") (pinfunction "OUT1_7") (pintype "unspecified"))
      (node (ref "U2") (pin "12") (pinfunction "12_12") (pintype "unspecified"))
    )
    (net (code "54") (name "Net-(STM1-OUT2)") (class "Default")
      (node (ref "STM1") (pin "6") (pinfunction "OUT2_6") (pintype "unspecified"))
      (node (ref "U2") (pin "13") (pinfunction "13_13") (pintype "unspecified"))
    )
    (net (code "55") (name "Net-(U1-D4)") (class "Default")
      (node (ref "6R3") (pin "1") (pinfunction "1_1") (pintype "unspecified"))
      (node (ref "U1") (pin "6") (pinfunction "D4_6") (pintype "unspecified"))
    )
    (net (code "56") (name "Net-(U1-D5)") (class "Default")
      (node (ref "R21") (pin "1") (pinfunction "1_1") (pintype "unspecified"))
      (node (ref "U1") (pin "7") (pinfunction "D5_7") (pintype "unspecified"))
    )
    (net (code "57") (name "Net-(U1-D9)") (class "Default")
      (node (ref "U1") (pin "11") (pinfunction "D9_11") (pintype "unspecified"))
      (node (ref "U6") (pin "3") (pinfunction "S1_3") (pintype "unspecified"))
    )
    (net (code "58") (name "Net-(U1-D10)") (class "Default")
      (node (ref "U1") (pin "12") (pinfunction "D10_12") (pintype "unspecified"))
      (node (ref "U7") (pin "3") (pinfunction "S1_3") (pintype "unspecified"))
    )
    (net (code "59") (name "Net-(U1-D11)") (class "Default")
      (node (ref "U1") (pin "13") (pinfunction "D11_13") (pintype "unspecified"))
      (node (ref "U8") (pin "3") (pinfunction "S1_3") (pintype "unspecified"))
    )
    (net (code "60") (name "Net-(U1-D14_A0)") (class "Default")
      (node (ref "R19") (pin "1") (pinfunction "1_1") (pintype "unspecified"))
      (node (ref "U1") (pin "37") (pinfunction "D14_A0_37") (pintype "unspecified"))
    )
    (net (code "61") (name "Net-(U1-D15_A1)") (class "Default")
      (node (ref "R11") (pin "1") (pinfunction "1_1") (pintype "unspecified"))
      (node (ref "U1") (pin "36") (pinfunction "D15_A1_36") (pintype "unspecified"))
    )
    (net (code "62") (name "Net-(U1-D16_A2)") (class "Default")
      (node (ref "R9") (pin "1") (pinfunction "1_1") (pintype "unspecified"))
      (node (ref "U1") (pin "35") (pinfunction "D16_A2_35") (pintype "unspecified"))
    )
    (net (code "63") (name "Net-(U1-D17_A3)") (class "Default")
      (node (ref "R14") (pin "1") (pinfunction "1_1") (pintype "unspecified"))
      (node (ref "U1") (pin "34") (pinfunction "D17_A3_34") (pintype "unspecified"))
    )
    (net (code "64") (name "Net-(U1-D20_A6)") (class "Default")
      (node (ref "R15") (pin "1") (pinfunction "1_1") (pintype "unspecified"))
      (node (ref "U1") (pin "31") (pinfunction "D20_A6_31") (pintype "unspecified"))
    )
    (net (code "65") (name "Net-(U1-D21_A7)") (class "Default")
      (node (ref "R4") (pin "1") (pinfunction "1_1") (pintype "unspecified"))
      (node (ref "U1") (pin "30") (pinfunction "D21_A7_30") (pintype "unspecified"))
    )
    (net (code "66") (name "Net-(U1-D22_A8)") (class "Default")
      (node (ref "R3") (pin "1") (pinfunction "1_1") (pintype "unspecified"))
      (node (ref "U1") (pin "29") (pinfunction "D22_A8_29") (pintype "unspecified"))
    )
    (net (code "67") (name "Net-(U1-D23_A9)") (class "Default")
      (node (ref "R6") (pin "1") (pinfunction "1_1") (pintype "unspecified"))
      (node (ref "U1") (pin "28") (pinfunction "D23_A9_28") (pintype "unspecified"))
    )
    (net (code "68") (name "Net-(U1-D32)") (class "Default")
      (node (ref "6R2") (pin "1") (pinfunction "1_1") (pintype "unspecified"))
      (node (ref "U1") (pin "24") (pinfunction "D32_24") (pintype "unspecified"))
    )
    (net (code "69") (name "Net-(U1-D33)") (class "Default")
      (node (ref "6R1") (pin "1") (pinfunction "1_1") (pintype "unspecified"))
      (node (ref "U1") (pin "48") (pinfunction "D33_48") (pintype "unspecified"))
    )
    (net (code "70") (name "Net-(U1-D34)") (class "Default")
      (node (ref "R30") (pin "1") (pinfunction "1_1") (pintype "unspecified"))
      (node (ref "U1") (pin "47") (pinfunction "D34_47") (pintype "unspecified"))
    )
    (net (code "71") (name "Net-(U1-D35)") (class "Default")
      (node (ref "R29") (pin "1") (pinfunction "1_1") (pintype "unspecified"))
      (node (ref "U1") (pin "46") (pinfunction "D35_46") (pintype "unspecified"))
    )
    (net (code "72") (name "Net-(U1-D36)") (class "Default")
      (node (ref "U1") (pin "45") (pinfunction "D36_45") (pintype "unspecified"))
      (node (ref "U2") (pin "10") (pinfunction "10_10") (pintype "unspecified"))
    )
    (net (code "73") (name "Net-(U1-D37)") (class "Default")
      (node (ref "U1") (pin "44") (pinfunction "D37_44") (pintype "unspecified"))
      (node (ref "U2") (pin "8") (pinfunction "8_8") (pintype "unspecified"))
    )
    (net (code "74") (name "Net-(U1-D38_A14)") (class "Default")
      (node (ref "U1") (pin "43") (pinfunction "D38_A14_43") (pintype "unspecified"))
      (node (ref "U2") (pin "3") (pinfunction "3_3") (pintype "unspecified"))
    )
    (net (code "75") (name "Net-(U1-D39_A15)") (class "Default")
      (node (ref "R1") (pin "1") (pinfunction "1_1") (pintype "unspecified"))
      (node (ref "U1") (pin "42") (pinfunction "D39_A15_42") (pintype "unspecified"))
    )
    (net (code "76") (name "Net-(U1-D40_A16)") (class "Default")
      (node (ref "R16") (pin "1") (pinfunction "1_1") (pintype "unspecified"))
      (node (ref "U1") (pin "41") (pinfunction "D40_A16_41") (pintype "unspecified"))
    )
    (net (code "77") (name "Net-(U1-D41_A17)") (class "Default")
      (node (ref "R18") (pin "1") (pinfunction "1_1") (pintype "unspecified"))
      (node (ref "U1") (pin "40") (pinfunction "D41_A17_40") (pintype "unspecified"))
    )
    (net (code "78") (name "Net-(U4-EN)") (class "Default")
      (node (ref "R21") (pin "2") (pinfunction "2_2") (pintype "unspecified"))
      (node (ref "U4") (pin "4") (pinfunction "EN_4") (pintype "unspecified"))
    )
    (net (code "79") (name "Net-(U6-A)") (class "Default")
      (node (ref "R24") (pin "1") (pinfunction "1_1") (pintype "unspecified"))
      (node (ref "U6") (pin "1") (pinfunction "A_1") (pintype "unspecified"))
    )
    (net (code "80") (name "Net-(U7-A)") (class "Default")
      (node (ref "R23") (pin "1") (pinfunction "1_1") (pintype "unspecified"))
      (node (ref "U7") (pin "1") (pinfunction "A_1") (pintype "unspecified"))
    )
    (net (code "81") (name "Net-(U8-A)") (class "Default")
      (node (ref "R22") (pin "1") (pinfunction "1_1") (pintype "unspecified"))
      (node (ref "U8") (pin "1") (pinfunction "A_1") (pintype "unspecified"))
    )
    (net (code "82") (name "Net-(VNQ1-EP_(VCC))") (class "Default")
      (node (ref "BV1") (pin "5") (pinfunction "VBB_5") (pintype "unspecified"))
      (node (ref "BV1") (pin "6") (pinfunction "VBB_6") (pintype "unspecified"))
      (node (ref "BV1") (pin "7") (pinfunction "VBB_7") (pintype "unspecified"))
      (node (ref "BV1") (pin "8") (pinfunction "VBB_8") (pintype "unspecified"))
      (node (ref "BV2") (pin "5") (pinfunction "VBB_5") (pintype "unspecified"))
      (node (ref "BV2") (pin "6") (pinfunction "VBB_6") (pintype "unspecified"))
      (node (ref "BV2") (pin "7") (pinfunction "VBB_7") (pintype "unspecified"))
      (node (ref "BV2") (pin "8") (pinfunction "VBB_8") (pintype "unspecified"))
      (node (ref "FH2") (pin "1") (pinfunction "1_1") (pintype "unspecified"))
      (node (ref "P1") (pin "1") (pinfunction "1_1") (pintype "unspecified"))
      (node (ref "R22") (pin "2") (pinfunction "2_2") (pintype "unspecified"))
      (node (ref "VNQ1") (pin "11") (pinfunction "EP_(VCC)_11") (pintype "bidirectional"))
    )
    (net (code "83") (name "Net-(VNQ1-GND)") (class "Default")
      (node (ref "D2") (pin "2") (pinfunction "2_2") (pintype "unspecified"))
      (node (ref "R7") (pin "2") (pinfunction "2_2") (pintype "unspecified"))
      (node (ref "VNQ1") (pin "5") (pinfunction "GND_5") (pintype "bidirectional"))
    )
    (net (code "84") (name "Net-(VNQ1-INPUT_2)") (class "Default")
      (node (ref "R4") (pin "2") (pinfunction "2_2") (pintype "unspecified"))
      (node (ref "VNQ1") (pin "9") (pinfunction "INPUT_2_9") (pintype "bidirectional"))
    )
    (net (code "85") (name "Net-(VNQ1-INPUT_3)") (class "Default")
      (node (ref "R3") (pin "2") (pinfunction "2_2") (pintype "unspecified"))
      (node (ref "VNQ1") (pin "8") (pinfunction "INPUT_3_8") (pintype "bidirectional"))
    )
    (net (code "86") (name "Net-(VNQ1-INPUT_4)") (class "Default")
      (node (ref "R6") (pin "2") (pinfunction "2_2") (pintype "unspecified"))
      (node (ref "VNQ1") (pin "7") (pinfunction "INPUT_4_7") (pintype "bidirectional"))
    )
    (net (code "87") (name "Net-(VNQ1-OUTPUT_2)") (class "Default")
      (node (ref "J1") (pin "2") (pinfunction "2_2") (pintype "input"))
      (node (ref "U9") (pin "2") (pinfunction "2_2") (pintype "unspecified"))
      (node (ref "VNQ1") (pin "2") (pinfunction "OUTPUT_2_2") (pintype "bidirectional"))
    )
    (net (code "88") (name "Net-(VNQ1-OUTPUT_3)") (class "Default")
      (node (ref "J1") (pin "6") (pinfunction "6_6") (pintype "input"))
      (node (ref "VNQ1") (pin "3") (pinfunction "OUTPUT_3_3") (pintype "bidirectional"))
    )
    (net (code "89") (name "Net-(VNQ1-OUTPUT_4)") (class "Default")
      (node (ref "J1") (pin "7") (pinfunction "7_7") (pintype "input"))
      (node (ref "VNQ1") (pin "4") (pinfunction "OUTPUT_4_4") (pintype "bidirectional"))
    )
    (net (code "90") (name "Net-(VNQ2-EP_(VCC))") (class "Default")
      (node (ref "FH3") (pin "1") (pinfunction "1_1") (pintype "unspecified"))
      (node (ref "P3") (pin "1") (pinfunction "1_1") (pintype "unspecified"))
      (node (ref "R23") (pin "2") (pinfunction "2_2") (pintype "unspecified"))
      (node (ref "VNQ2") (pin "11") (pinfunction "EP_(VCC)_11") (pintype "bidirectional"))
      (node (ref "VNQ3") (pin "11") (pinfunction "EP_(VCC)_11") (pintype "bidirectional"))
    )
    (net (code "91") (name "Net-(VNQ2-GND)") (class "Default")
      (node (ref "D4") (pin "2") (pinfunction "2_2") (pintype "unspecified"))
      (node (ref "R17") (pin "2") (pinfunction "2_2") (pintype "unspecified"))
      (node (ref "VNQ2") (pin "5") (pinfunction "GND_5") (pintype "bidirectional"))
    )
    (net (code "92") (name "Net-(VNQ2-INPUT_1)") (class "Default")
      (node (ref "R11") (pin "2") (pinfunction "2_2") (pintype "unspecified"))
      (node (ref "VNQ2") (pin "10") (pinfunction "INPUT_1_10") (pintype "bidirectional"))
    )
    (net (code "93") (name "Net-(VNQ2-INPUT_2)") (class "Default")
      (node (ref "R9") (pin "2") (pinfunction "2_2") (pintype "unspecified"))
      (node (ref "VNQ2") (pin "9") (pinfunction "INPUT_2_9") (pintype "bidirectional"))
    )
    (net (code "94") (name "Net-(VNQ2-INPUT_3)") (class "Default")
      (node (ref "R14") (pin "2") (pinfunction "2_2") (pintype "unspecified"))
      (node (ref "VNQ2") (pin "8") (pinfunction "INPUT_3_8") (pintype "bidirectional"))
    )
    (net (code "95") (name "Net-(VNQ2-INPUT_4)") (class "Default")
      (node (ref "R15") (pin "2") (pinfunction "2_2") (pintype "unspecified"))
      (node (ref "VNQ2") (pin "7") (pinfunction "INPUT_4_7") (pintype "bidirectional"))
    )
    (net (code "96") (name "Net-(VNQ2-OUTPUT_1)") (class "Default")
      (node (ref "U2") (pin "14") (pinfunction "14_14") (pintype "unspecified"))
      (node (ref "VNQ2") (pin "1") (pinfunction "OUTPUT_1_1") (pintype "bidirectional"))
    )
    (net (code "97") (name "Net-(VNQ2-OUTPUT_2)") (class "Default")
      (node (ref "J1") (pin "5") (pinfunction "5_5") (pintype "input"))
      (node (ref "VNQ2") (pin "2") (pinfunction "OUTPUT_2_2") (pintype "bidirectional"))
    )
    (net (code "98") (name "Net-(VNQ2-OUTPUT_3)") (class "Default")
      (node (ref "J1") (pin "4") (pinfunction "4_4") (pintype "input"))
      (node (ref "VNQ2") (pin "3") (pinfunction "OUTPUT_3_3") (pintype "bidirectional"))
    )
    (net (code "99") (name "Net-(VNQ2-OUTPUT_4)") (class "Default")
      (node (ref "J1") (pin "3") (pinfunction "3_3") (pintype "input"))
      (node (ref "VNQ2") (pin "4") (pinfunction "OUTPUT_4_4") (pintype "bidirectional"))
    )
    (net (code "100") (name "Net-(VNQ3-GND)") (class "Default")
      (node (ref "D1") (pin "2") (pinfunction "2_2") (pintype "unspecified"))
      (node (ref "R10") (pin "2") (pinfunction "2_2") (pintype "unspecified"))
      (node (ref "VNQ3") (pin "5") (pinfunction "GND_5") (pintype "bidirectional"))
    )
    (net (code "101") (name "Net-(VNQ3-INPUT_1)") (class "Default")
      (node (ref "R1") (pin "2") (pinfunction "2_2") (pintype "unspecified"))
      (node (ref "VNQ3") (pin "10") (pinfunction "INPUT_1_10") (pintype "bidirectional"))
    )
    (net (code "102") (name "Net-(VNQ3-INPUT_2)") (class "Default")
      (node (ref "R16") (pin "2") (pinfunction "2_2") (pintype "unspecified"))
      (node (ref "VNQ3") (pin "9") (pinfunction "INPUT_2_9") (pintype "bidirectional"))
    )
    (net (code "103") (name "Net-(VNQ3-INPUT_3)") (class "Default")
      (node (ref "R18") (pin "2") (pinfunction "2_2") (pintype "unspecified"))
      (node (ref "VNQ3") (pin "8") (pinfunction "INPUT_3_8") (pintype "bidirectional"))
    )
    (net (code "104") (name "Net-(VNQ3-INPUT_4)") (class "Default")
      (node (ref "R19") (pin "2") (pinfunction "2_2") (pintype "unspecified"))
      (node (ref "VNQ3") (pin "7") (pinfunction "INPUT_4_7") (pintype "bidirectional"))
    )
    (net (code "105") (name "Net-(VNQ3-OUTPUT_1)") (class "Default")
      (node (ref "J1") (pin "9") (pinfunction "9_9") (pintype "input"))
      (node (ref "U9") (pin "3") (pinfunction "3_3") (pintype "unspecified"))
      (node (ref "VNQ3") (pin "1") (pinfunction "OUTPUT_1_1") (pintype "bidirectional"))
    )
    (net (code "106") (name "Net-(VNQ3-OUTPUT_2)") (class "Default")
      (node (ref "U2") (pin "5") (pinfunction "5_5") (pintype "unspecified"))
      (node (ref "VNQ3") (pin "2") (pinfunction "OUTPUT_2_2") (pintype "bidirectional"))
    )
    (net (code "107") (name "Net-(VNQ3-OUTPUT_3)") (class "Default")
      (node (ref "U2") (pin "4") (pinfunction "4_4") (pintype "unspecified"))
      (node (ref "VNQ3") (pin "3") (pinfunction "OUTPUT_3_3") (pintype "bidirectional"))
    )
    (net (code "108") (name "Net-(VNQ3-OUTPUT_4)") (class "Default")
      (node (ref "J1") (pin "8") (pinfunction "8_8") (pintype "input"))
      (node (ref "VNQ3") (pin "4") (pinfunction "OUTPUT_4_4") (pintype "bidirectional"))
    )
    (net (code "109") (name "unconnected-(ADC1-ALERT{slash}RDY-Pad2)") (class "Default")
      (node (ref "ADC1") (pin "2") (pinfunction "ALERT/RDY_2") (pintype "unspecified"))
    )
    (net (code "110") (name "unconnected-(ADC2-ALERT{slash}RDY-Pad2)") (class "Default")
      (node (ref "ADC2") (pin "2") (pinfunction "ALERT/RDY_2") (pintype "unspecified"))
    )
    (net (code "111") (name "unconnected-(BV1-ST-Pad2)") (class "Default")
      (node (ref "BV1") (pin "2") (pinfunction "ST_2") (pintype "unspecified"))
    )
    (net (code "112") (name "unconnected-(J1-MH1-Pad10)") (class "Default")
      (node (ref "J1") (pin "10") (pinfunction "MH1_10") (pintype "input"))
    )
    (net (code "113") (name "unconnected-(J1-MH2-Pad11)") (class "Default")
      (node (ref "J1") (pin "11") (pinfunction "MH2_11") (pintype "input"))
    )
    (net (code "114") (name "unconnected-(Q3-1IN-Pad1)") (class "Default")
      (node (ref "Q3") (pin "1") (pinfunction "1IN_1") (pintype "unspecified"))
    )
    (net (code "115") (name "unconnected-(Q3-2IN-Pad2)") (class "Default")
      (node (ref "Q3") (pin "2") (pinfunction "2IN_2") (pintype "unspecified"))
    )
    (net (code "116") (name "unconnected-(Q3-8IN-Pad8)") (class "Default")
      (node (ref "Q3") (pin "8") (pinfunction "8IN_8") (pintype "unspecified"))
    )
    (net (code "117") (name "unconnected-(Q3-COM-Pad10)") (class "Default")
      (node (ref "Q3") (pin "10") (pinfunction "COM_10") (pintype "unspecified"))
    )
    (net (code "118") (name "unconnected-(Q3-OUT1-Pad18)") (class "Default")
      (node (ref "Q3") (pin "18") (pinfunction "OUT1_18") (pintype "unspecified"))
    )
    (net (code "119") (name "unconnected-(Q3-OUT2-Pad17)") (class "Default")
      (node (ref "Q3") (pin "17") (pinfunction "OUT2_17") (pintype "unspecified"))
    )
    (net (code "120") (name "unconnected-(Q3-OUT8-Pad11)") (class "Default")
      (node (ref "Q3") (pin "11") (pinfunction "OUT8_11") (pintype "unspecified"))
    )
    (net (code "121") (name "unconnected-(REG1-EN-Pad1)") (class "Default")
      (node (ref "REG1") (pin "1") (pinfunction "EN_1") (pintype "unspecified"))
    )
    (net (code "122") (name "unconnected-(REG2-EN-Pad1)") (class "Default")
      (node (ref "REG2") (pin "1") (pinfunction "EN_1") (pintype "unspecified"))
    )
    (net (code "123") (name "unconnected-(STM1-OC1#-Pad8)") (class "Default")
      (node (ref "STM1") (pin "8") (pinfunction "OC1#_8") (pintype "unspecified"))
    )
    (net (code "124") (name "unconnected-(STM1-OC2#-Pad5)") (class "Default")
      (node (ref "STM1") (pin "5") (pinfunction "OC2#_5") (pintype "unspecified"))
    )
    (net (code "125") (name "unconnected-(U1-3.3V-Pad15)") (class "Default")
      (node (ref "U1") (pin "15") (pinfunction "3.3V_15") (pintype "unspecified"))
    )
    (net (code "126") (name "unconnected-(U1-D13-Pad38)") (class "Default")
      (node (ref "U1") (pin "38") (pinfunction "D13_38") (pintype "unspecified"))
    )
    (net (code "127") (name "unconnected-(U1-Vusb-Pad49)") (class "Default")
      (node (ref "U1") (pin "49") (pinfunction "Vusb_49") (pintype "unspecified"))
    )
    (net (code "128") (name "unconnected-(U2-Shell_1-Pad16)") (class "Default")
      (node (ref "U2") (pin "16") (pinfunction "Shell_1_16") (pintype "unspecified"))
    )
    (net (code "129") (name "unconnected-(U2-Shell_2-Pad17)") (class "Default")
      (node (ref "U2") (pin "17") (pinfunction "Shell_2_17") (pintype "unspecified"))
    )
    (net (code "130") (name "unconnected-(U4-FAULT-Pad5)") (class "Default")
      (node (ref "U4") (pin "5") (pinfunction "FAULT_5") (pintype "unspecified"))
    )
    (net (code "131") (name "unconnected-(VNQ1-INPUT_1-Pad10)") (class "Default")
      (node (ref "VNQ1") (pin "10") (pinfunction "INPUT_1_10") (pintype "bidirectional"))
    )
    (net (code "132") (name "unconnected-(VNQ1-OUTPUT_1-Pad1)") (class "Default")
      (node (ref "VNQ1") (pin "1") (pinfunction "OUTPUT_1_1") (pintype "bidirectional"))
    )
    (net (code "133") (name "unconnected-(VNQ1-STATUS-Pad6)") (class "Default")
      (node (ref "VNQ1") (pin "6") (pinfunction "STATUS_6") (pintype "bidirectional"))
    )
    (net (code "134") (name "unconnected-(VNQ2-STATUS-Pad6)") (class "Default")
      (node (ref "VNQ2") (pin "6") (pinfunction "STATUS_6") (pintype "bidirectional"))
    )
    (net (code "135") (name "unconnected-(VNQ3-STATUS-Pad6)") (class "Default")
      (node (ref "VNQ3") (pin "6") (pinfunction "STATUS_6") (pintype "bidirectional"))
    )
  )
)
